# bumper.net
KiCad netlist of a schematic drawn in EAGLE
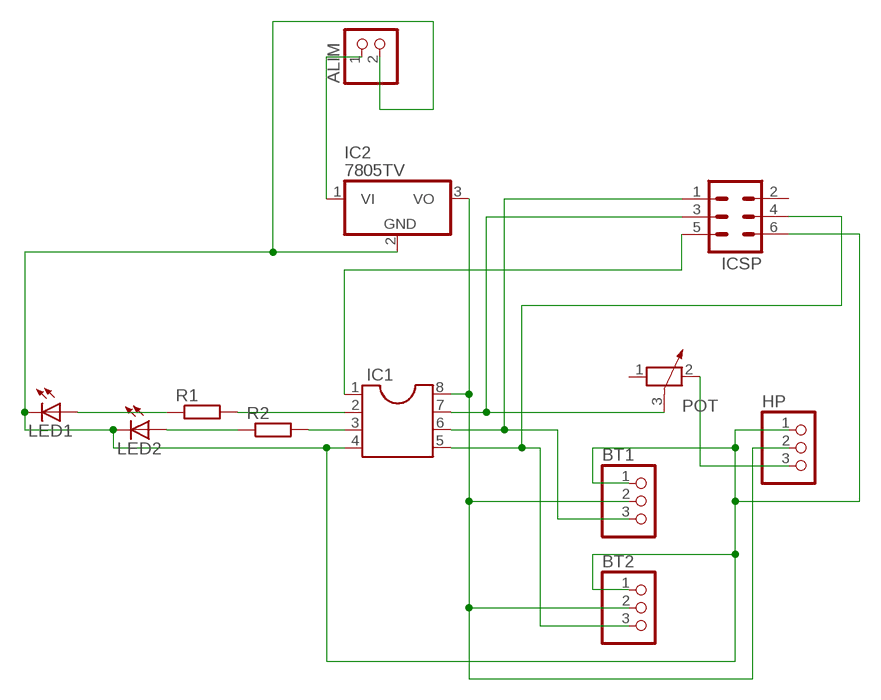
[diagram p0: schematic, sheet 1]

(export (version "E")
  (design (tool "Eeschema 10.0.6"))
  (components
    (comp (ref "ALIM")
      (value "PINHD-1X2")
      (footprint "eagle-import:1X02")
      (libsource (lib "eagle-import") (part "PINHD-1X2"))
    )
    (comp (ref "BT1")
      (value "PINHD-1X3")
      (footprint "eagle-import:1X03")
      (libsource (lib "eagle-import") (part "PINHD-1X3"))
    )
    (comp (ref "BT2")
      (value "PINHD-1X3")
      (footprint "eagle-import:1X03")
      (libsource (lib "eagle-import") (part "PINHD-1X3"))
    )
    (comp (ref "HP")
      (value "PINHD-1X3")
      (footprint "eagle-import:1X03")
      (libsource (lib "eagle-import") (part "PINHD-1X3"))
    )
    (comp (ref "IC1")
      (value "DIL8S")
      (footprint "eagle-import:SOCKET-08")
      (libsource (lib "eagle-import") (part "DIL8S"))
    )
    (comp (ref "IC2")
      (value "7805TV")
      (footprint "eagle-import:TO220V")
      (libsource (lib "eagle-import") (part "78TV05"))
    )
    (comp (ref "ICSP")
      (value "ML6")
      (footprint "eagle-import:ML6")
      (libsource (lib "eagle-import") (part "ML6"))
    )
    (comp (ref "LED1")
      (value "LED5MM")
      (footprint "eagle-import:LED5MM")
      (libsource (lib "eagle-import") (part "LED5MM"))
    )
    (comp (ref "LED2")
      (value "LED5MM")
      (footprint "eagle-import:LED5MM")
      (libsource (lib "eagle-import") (part "LED5MM"))
    )
    (comp (ref "POT")
      (value "POTENTIOMETER_PT-10")
      (footprint "eagle-import:PT-10")
      (libsource (lib "eagle-import") (part "POTENTIOMETER_PT-10"))
    )
    (comp (ref "R1")
      (value "R-EU_0204/7")
      (footprint "eagle-import:0204_7")
      (libsource (lib "eagle-import") (part "R-EU_0204/7"))
    )
    (comp (ref "R2")
      (value "R-EU_0204/7")
      (footprint "eagle-import:0204_7")
      (libsource (lib "eagle-import") (part "R-EU_0204/7"))
    )
  )
  (nets
    (net (code "1") (name "Net-(BT1-Pad3)") (class "Default")
      (node (ref "BT1") (pin "3") (pinfunction "3_3") (pintype "passive"))
      (node (ref "IC1") (pin "6") (pinfunction "6_6") (pintype "passive"))
      (node (ref "ICSP") (pin "1") (pinfunction "1_1") (pintype "passive"))
    )
    (net (code "2") (name "Net-(BT2-Pad3)") (class "Default")
      (node (ref "BT2") (pin "3") (pinfunction "3_3") (pintype "passive"))
      (node (ref "IC1") (pin "5") (pinfunction "5_5") (pintype "passive"))
      (node (ref "ICSP") (pin "4") (pinfunction "4_4") (pintype "passive"))
    )
    (net (code "3") (name "Net-(HP-Pad3)") (class "Default")
      (node (ref "HP") (pin "3") (pinfunction "3_3") (pintype "passive"))
      (node (ref "POT") (pin "2") (pinfunction "2_2") (pintype "passive"))
    )
    (net (code "4") (name "Net-(IC1-Pad1)") (class "Default")
      (node (ref "IC1") (pin "1") (pinfunction "1_1") (pintype "passive"))
      (node (ref "ICSP") (pin "5") (pinfunction "5_5") (pintype "passive"))
    )
    (net (code "5") (name "Net-(IC1-Pad2)") (class "Default")
      (node (ref "IC1") (pin "2") (pinfunction "2_2") (pintype "passive"))
      (node (ref "R1") (pin "2") (pinfunction "2_2") (pintype "passive"))
    )
    (net (code "6") (name "Net-(IC1-Pad3)") (class "Default")
      (node (ref "IC1") (pin "3") (pinfunction "3_3") (pintype "passive"))
      (node (ref "R2") (pin "2") (pinfunction "2_2") (pintype "passive"))
    )
    (net (code "7") (name "Net-(IC1-Pad7)") (class "Default")
      (node (ref "IC1") (pin "7") (pinfunction "7_7") (pintype "passive"))
      (node (ref "ICSP") (pin "3") (pinfunction "3_3") (pintype "passive"))
      (node (ref "POT") (pin "3") (pinfunction "3_3") (pintype "passive"))
    )
    (net (code "8") (name "Net-(IC2-GND)") (class "Default")
      (node (ref "ALIM") (pin "2") (pinfunction "2_2") (pintype "passive"))
      (node (ref "BT1") (pin "1") (pinfunction "1_1") (pintype "passive"))
      (node (ref "BT2") (pin "1") (pinfunction "1_1") (pintype "passive"))
      (node (ref "HP") (pin "1") (pinfunction "1_1") (pintype "passive"))
      (node (ref "IC1") (pin "4") (pinfunction "4_4") (pintype "passive"))
      (node (ref "IC2") (pin "2") (pinfunction "GND_2") (pintype "passive"))
      (node (ref "ICSP") (pin "6") (pinfunction "6_6") (pintype "passive"))
      (node (ref "LED1") (pin "K") (pinfunction "C_K") (pintype "passive"))
      (node (ref "LED2") (pin "K") (pinfunction "C_K") (pintype "passive"))
    )
    (net (code "9") (name "Net-(IC2-VI)") (class "Default")
      (node (ref "ALIM") (pin "1") (pinfunction "1_1") (pintype "passive"))
      (node (ref "IC2") (pin "1") (pinfunction "VI_1") (pintype "input"))
    )
    (net (code "10") (name "Net-(IC2-VO)") (class "Default")
      (node (ref "BT1") (pin "2") (pinfunction "2_2") (pintype "passive"))
      (node (ref "BT2") (pin "2") (pinfunction "2_2") (pintype "passive"))
      (node (ref "HP") (pin "2") (pinfunction "2_2") (pintype "passive"))
      (node (ref "IC1") (pin "8") (pinfunction "8_8") (pintype "passive"))
      (node (ref "IC2") (pin "3") (pinfunction "VO_3") (pintype "passive"))
    )
    (net (code "11") (name "Net-(LED1-PadA)") (class "Default")
      (node (ref "LED1") (pin "A") (pinfunction "A_A") (pintype "passive"))
      (node (ref "R1") (pin "1") (pinfunction "1_1") (pintype "passive"))
    )
    (net (code "12") (name "Net-(LED2-PadA)") (class "Default")
      (node (ref "LED2") (pin "A") (pinfunction "A_A") (pintype "passive"))
      (node (ref "R2") (pin "1") (pinfunction "1_1") (pintype "passive"))
    )
    (net (code "13") (name "unconnected-(ICSP-Pad2)") (class "Default")
      (node (ref "ICSP") (pin "2") (pinfunction "2_2") (pintype "passive"))
    )
    (net (code "14") (name "unconnected-(POT-Pad1)") (class "Default")
      (node (ref "POT") (pin "1") (pinfunction "1_1") (pintype "passive"))
    )
  )
)
